# AMU-S26-V00-DAUGHTERShutdown.net
KiCad netlist of a schematic drawn in Altium Designer
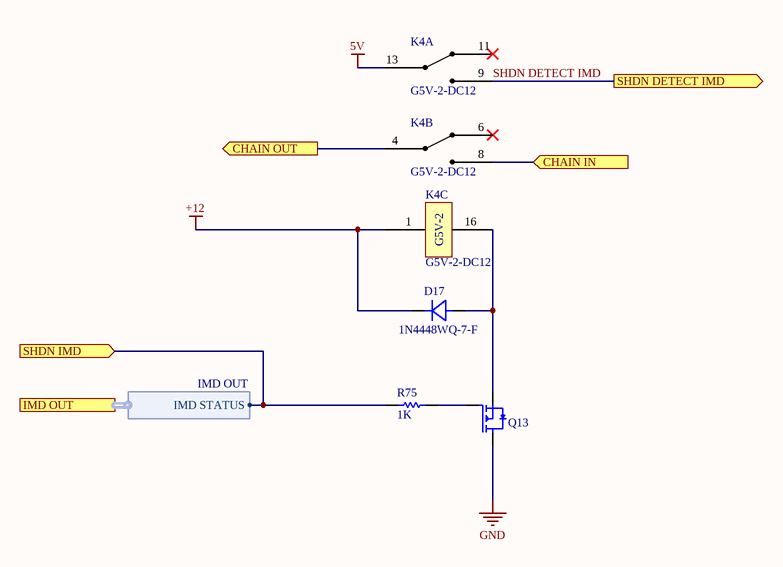
[diagram p0: AMU-S26-V00-DAUGHTERShutdown.SchDoc]

(export (version "E")
  (design (tool "Eeschema 10.0.6"))
  (components
    (comp (ref "D17")
      (value "1N4448WQ-7-F")
      (footprint "SMA")
      (description "Diode, SMD, 75V, 5%, 250mA, SOD123")
      (fields
        (field (name "MANUFACTURER") "ON Semiconductor / Fairchild")
        (field (name "MANUFACTURER PART NUMBER") "1N914BWS")
      )
      (libsource (lib "QUTMS_DiodeLibrary") (part "1N4448WQ-7-F"))
    )
    (comp (ref "K4")
      (value "G5V-2-DC12")
      (footprint "G5V-2")
      (description "General Purpose Relay DPDT (2 Form C) Through Hole, 12V, 2A")
      (libsource (lib "QUTMS_RelayLibrary") (part "G5V-2-DC12"))
    )
    (comp (ref "Q13")
      (value "~")
      (footprint "PMV15UNEAR")
      (description "MOSFET N-CH, 20V, SOT23")
      (fields (field (name "MANUFACTURER") "Nexperia"))
      (libsource (lib "CellMonitor") (part "PMV15UNEAR"))
    )
    (comp (ref "R75")
      (value "1K")
      (footprint "Res_ThinFilm_0603")
      (description "Resistor, SMD, 1k, 0.1W, 5%, 0603")
      (libsource (lib "StandardResistors") (part "1k 5% 0603"))
    )
  )
  (nets
    (net (code "3") (name "+12") (class "Default")
      (node (ref "D17") (pin "K") (pinfunction "Cathode_K") (pintype "passive"))
      (node (ref "K4") (pin "1") (pinfunction "1_1") (pintype "passive"))
    )
    (net (code "4") (name "/CHAIN IN") (class "Default")
      (node (ref "K4") (pin "8") (pinfunction "8_8") (pintype "passive"))
    )
    (net (code "5") (name "/CHAIN OUT") (class "Default")
      (node (ref "K4") (pin "4") (pinfunction "4_4") (pintype "passive"))
    )
    (net (code "6") (name "/SHDN DETECT IMD") (class "Default")
      (node (ref "K4") (pin "9") (pinfunction "9_9") (pintype "passive"))
    )
    (net (code "7") (name "/SHDN IMD") (class "Default")
      (node (ref "R75") (pin "1") (pinfunction "1_1") (pintype "passive"))
    )
    (net (code "9") (name "5V") (class "Default")
      (node (ref "K4") (pin "13") (pinfunction "13_13") (pintype "passive"))
    )
    (net (code "10") (name "GND") (class "Default")
      (node (ref "Q13") (pin "D") (pinfunction "Drain_D") (pintype "passive"))
    )
    (net (code "11") (name "Net-(D17-Anode)") (class "Default")
      (node (ref "D17") (pin "A") (pinfunction "Anode_A") (pintype "passive"))
      (node (ref "K4") (pin "16") (pinfunction "16_16") (pintype "passive"))
      (node (ref "Q13") (pin "S") (pinfunction "Source_S") (pintype "passive"))
    )
    (net (code "12") (name "Net-(Q13-Gate)") (class "Default")
      (node (ref "Q13") (pin "G") (pinfunction "Gate_G") (pintype "passive"))
      (node (ref "R75") (pin "2") (pinfunction "2_2") (pintype "passive"))
    )
    (net (code "13") (name "unconnected-(K4-Pad6)") (class "Default")
      (node (ref "K4") (pin "6") (pinfunction "6_6") (pintype "passive+no_connect"))
    )
    (net (code "14") (name "unconnected-(K4-Pad11)") (class "Default")
      (node (ref "K4") (pin "11") (pinfunction "11_11") (pintype "passive+no_connect"))
    )
  )
)
